# phoreo.net
KiCad netlist of a schematic drawn in EAGLE
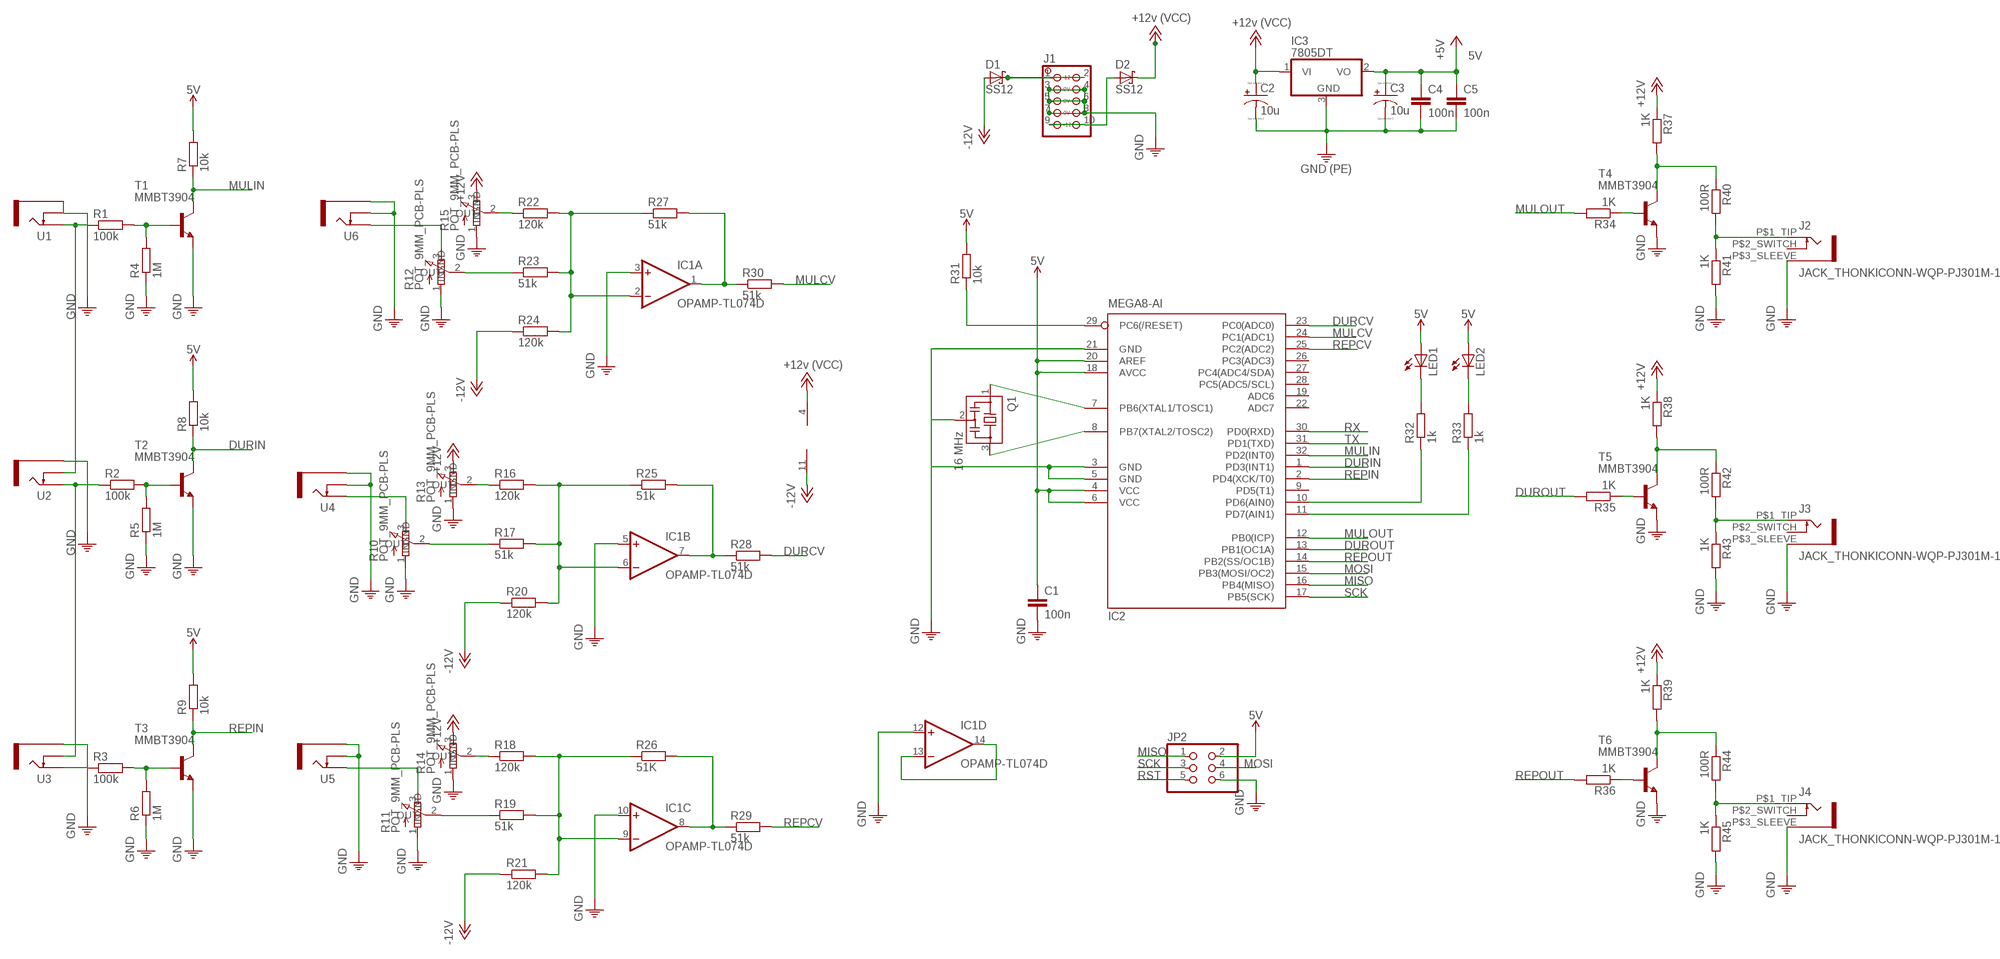
[diagram p0: schematic, sheet 1]

(export (version "E")
  (design (tool "Eeschema 10.0.6"))
  (components
    (comp (ref "C1")
      (value "100n")
      (footprint "eagle-import:C0603K")
      (libsource (lib "eagle-import") (part "CAPACITOR-EUC0603K"))
    )
    (comp (ref "C2")
      (value "10u")
      (footprint "eagle-import:PANASONIC_B")
      (libsource (lib "eagle-import") (part "CAPACITOR_POLARIZED-USB"))
    )
    (comp (ref "C3")
      (value "10u")
      (footprint "eagle-import:PANASONIC_B")
      (libsource (lib "eagle-import") (part "CAPACITOR_POLARIZED-USB"))
    )
    (comp (ref "C4")
      (value "100n")
      (footprint "eagle-import:C0603")
      (libsource (lib "eagle-import") (part "CAPACITOR-EUC0603"))
    )
    (comp (ref "C5")
      (value "100n")
      (footprint "eagle-import:C0603")
      (libsource (lib "eagle-import") (part "CAPACITOR-EUC0603"))
    )
    (comp (ref "D1")
      (value "SS12")
      (footprint "eagle-import:SMA_DO214AC")
      (libsource (lib "eagle-import") (part "D_SCHOTTKY-SMA"))
    )
    (comp (ref "D2")
      (value "SS12")
      (footprint "eagle-import:SMA_DO214AC")
      (libsource (lib "eagle-import") (part "D_SCHOTTKY-SMA"))
    )
    (comp (ref "IC1")
      (value "OPAMP-TL074D")
      (footprint "eagle-import:SO14")
      (libsource (lib "eagle-import") (part "OPAMP-TL074D"))
    )
    (comp (ref "IC2")
      (value "MEGA8-AI")
      (footprint "eagle-import:TQFP32-08")
      (fields (field (name "MPN") "ATMEGA8-16AU"))
      (libsource (lib "eagle-import") (part "MEGA8-AI"))
    )
    (comp (ref "IC3")
      (value "7805DT")
      (footprint "eagle-import:TO252")
      (libsource (lib "eagle-import") (part "78DT05"))
    )
    (comp (ref "J1")
      (value "HEADER-EUROPWR_2X05-OPEN")
      (footprint "eagle-import:2X05_EUROPWR_OPEN")
      (libsource (lib "eagle-import") (part "HEADER-EUROPWR_2X05-OPEN"))
    )
    (comp (ref "J2")
      (value "JACK_THONKICONN-WQP-PJ301M-12")
      (footprint "eagle-import:WQP-PJ301M-12_JACK")
      (libsource (lib "eagle-import") (part "JACK_THONKICONN-WQP-PJ301M-12"))
    )
    (comp (ref "J3")
      (value "JACK_THONKICONN-WQP-PJ301M-12")
      (footprint "eagle-import:WQP-PJ301M-12_JACK")
      (libsource (lib "eagle-import") (part "JACK_THONKICONN-WQP-PJ301M-12"))
    )
    (comp (ref "J4")
      (value "JACK_THONKICONN-WQP-PJ301M-12")
      (footprint "eagle-import:WQP-PJ301M-12_JACK")
      (libsource (lib "eagle-import") (part "JACK_THONKICONN-WQP-PJ301M-12"))
    )
    (comp (ref "JP2")
      (value "PINHD-2X3")
      (footprint "eagle-import:2X03")
      (libsource (lib "eagle-import") (part "PINHD-2X3"))
    )
    (comp (ref "LED1")
      (value "LED3MM")
      (footprint "eagle-import:LED3MM")
      (libsource (lib "eagle-import") (part "LED3MM"))
    )
    (comp (ref "LED2")
      (value "LED3MM")
      (footprint "eagle-import:LED3MM")
      (libsource (lib "eagle-import") (part "LED3MM"))
    )
    (comp (ref "Q1")
      (value "16 MHz")
      (footprint "eagle-import:CSTCR6M")
      (fields (field (name "MPN") "CSTCR6M00G53-R0"))
      (libsource (lib "eagle-import") (part "CSTCR6M00G53Z"))
    )
    (comp (ref "R1")
      (value "100k")
      (footprint "eagle-import:R0603")
      (libsource (lib "eagle-import") (part "RESISTOR-EU_R0603"))
    )
    (comp (ref "R2")
      (value "100k")
      (footprint "eagle-import:R0603")
      (libsource (lib "eagle-import") (part "RESISTOR-EU_R0603"))
    )
    (comp (ref "R3")
      (value "100k")
      (footprint "eagle-import:R0603")
      (libsource (lib "eagle-import") (part "RESISTOR-EU_R0603"))
    )
    (comp (ref "R4")
      (value "1M")
      (footprint "eagle-import:R0603")
      (libsource (lib "eagle-import") (part "RESISTOR-EU_R0603"))
    )
    (comp (ref "R5")
      (value "1M")
      (footprint "eagle-import:R0603")
      (libsource (lib "eagle-import") (part "RESISTOR-EU_R0603"))
    )
    (comp (ref "R6")
      (value "1M")
      (footprint "eagle-import:R0603")
      (libsource (lib "eagle-import") (part "RESISTOR-EU_R0603"))
    )
    (comp (ref "R7")
      (value "10k")
      (footprint "eagle-import:R0603")
      (libsource (lib "eagle-import") (part "RESISTOR-EU_R0603"))
    )
    (comp (ref "R8")
      (value "10k")
      (footprint "eagle-import:R0603")
      (libsource (lib "eagle-import") (part "RESISTOR-EU_R0603"))
    )
    (comp (ref "R9")
      (value "10k")
      (footprint "eagle-import:R0603")
      (libsource (lib "eagle-import") (part "RESISTOR-EU_R0603"))
    )
    (comp (ref "R10")
      (value "POT_9MM_PCB-PLS")
      (footprint "eagle-import:9MM_PLS")
      (libsource (lib "eagle-import") (part "POT_9MM_PCB-PLS"))
    )
    (comp (ref "R11")
      (value "POT_9MM_PCB-PLS")
      (footprint "eagle-import:9MM_PLS")
      (libsource (lib "eagle-import") (part "POT_9MM_PCB-PLS"))
    )
    (comp (ref "R12")
      (value "POT_9MM_PCB-PLS")
      (footprint "eagle-import:9MM_PLS")
      (libsource (lib "eagle-import") (part "POT_9MM_PCB-PLS"))
    )
    (comp (ref "R13")
      (value "POT_9MM_PCB-PLS")
      (footprint "eagle-import:9MM_PLS")
      (libsource (lib "eagle-import") (part "POT_9MM_PCB-PLS"))
    )
    (comp (ref "R14")
      (value "POT_9MM_PCB-PLS")
      (footprint "eagle-import:9MM_PLS")
      (libsource (lib "eagle-import") (part "POT_9MM_PCB-PLS"))
    )
    (comp (ref "R15")
      (value "POT_9MM_PCB-PLS")
      (footprint "eagle-import:9MM_PLS")
      (libsource (lib "eagle-import") (part "POT_9MM_PCB-PLS"))
    )
    (comp (ref "R16")
      (value "120k")
      (footprint "eagle-import:R0603")
      (libsource (lib "eagle-import") (part "RESISTOR-EU_R0603"))
    )
    (comp (ref "R17")
      (value "51k")
      (footprint "eagle-import:R0603")
      (libsource (lib "eagle-import") (part "RESISTOR-EU_R0603"))
    )
    (comp (ref "R18")
      (value "120k")
      (footprint "eagle-import:R0603")
      (libsource (lib "eagle-import") (part "RESISTOR-EU_R0603"))
    )
    (comp (ref "R19")
      (value "51k")
      (footprint "eagle-import:R0603")
      (libsource (lib "eagle-import") (part "RESISTOR-EU_R0603"))
    )
    (comp (ref "R20")
      (value "120k")
      (footprint "eagle-import:R0603")
      (libsource (lib "eagle-import") (part "RESISTOR-EU_R0603"))
    )
    (comp (ref "R21")
      (value "120k")
      (footprint "eagle-import:R0603")
      (libsource (lib "eagle-import") (part "RESISTOR-EU_R0603"))
    )
    (comp (ref "R22")
      (value "120k")
      (footprint "eagle-import:R0603")
      (libsource (lib "eagle-import") (part "RESISTOR-EU_R0603"))
    )
    (comp (ref "R23")
      (value "51k")
      (footprint "eagle-import:R0603")
      (libsource (lib "eagle-import") (part "RESISTOR-EU_R0603"))
    )
    (comp (ref "R24")
      (value "120k")
      (footprint "eagle-import:R0603")
      (libsource (lib "eagle-import") (part "RESISTOR-EU_R0603"))
    )
    (comp (ref "R25")
      (value "51k")
      (footprint "eagle-import:R0603")
      (libsource (lib "eagle-import") (part "RESISTOR-EU_R0603"))
    )
    (comp (ref "R26")
      (value "51K")
      (footprint "eagle-import:R0603")
      (libsource (lib "eagle-import") (part "RESISTOR-EU_R0603"))
    )
    (comp (ref "R27")
      (value "51k")
      (footprint "eagle-import:R0603")
      (libsource (lib "eagle-import") (part "RESISTOR-EU_R0603"))
    )
    (comp (ref "R28")
      (value "51k")
      (footprint "eagle-import:R0603")
      (libsource (lib "eagle-import") (part "RESISTOR-EU_R0603"))
    )
    (comp (ref "R29")
      (value "51k")
      (footprint "eagle-import:R0603")
      (libsource (lib "eagle-import") (part "RESISTOR-EU_R0603"))
    )
    (comp (ref "R30")
      (value "51k")
      (footprint "eagle-import:R0603")
      (libsource (lib "eagle-import") (part "RESISTOR-EU_R0603"))
    )
    (comp (ref "R31")
      (value "10k")
      (footprint "eagle-import:R0603")
      (libsource (lib "eagle-import") (part "RESISTOR-EU_R0603"))
    )
    (comp (ref "R32")
      (value "1k")
      (footprint "eagle-import:R0603")
      (libsource (lib "eagle-import") (part "RESISTOR-EU_R0603"))
    )
    (comp (ref "R33")
      (value "1k")
      (footprint "eagle-import:R0603")
      (libsource (lib "eagle-import") (part "RESISTOR-EU_R0603"))
    )
    (comp (ref "R34")
      (value "1K")
      (footprint "eagle-import:R0603")
      (libsource (lib "eagle-import") (part "RESISTOR-EU_R0603"))
    )
    (comp (ref "R35")
      (value "1K")
      (footprint "eagle-import:R0603")
      (libsource (lib "eagle-import") (part "RESISTOR-EU_R0603"))
    )
    (comp (ref "R36")
      (value "1K")
      (footprint "eagle-import:R0603")
      (libsource (lib "eagle-import") (part "RESISTOR-EU_R0603"))
    )
    (comp (ref "R37")
      (value "1K")
      (footprint "eagle-import:R0603")
      (libsource (lib "eagle-import") (part "RESISTOR-EU_R0603"))
    )
    (comp (ref "R38")
      (value "1K")
      (footprint "eagle-import:R0603")
      (libsource (lib "eagle-import") (part "RESISTOR-EU_R0603"))
    )
    (comp (ref "R39")
      (value "1K")
      (footprint "eagle-import:R0603")
      (libsource (lib "eagle-import") (part "RESISTOR-EU_R0603"))
    )
    (comp (ref "R40")
      (value "100R")
      (footprint "eagle-import:R0603")
      (libsource (lib "eagle-import") (part "RESISTOR-EU_R0603"))
    )
    (comp (ref "R41")
      (value "1K")
      (footprint "eagle-import:R0603")
      (libsource (lib "eagle-import") (part "RESISTOR-EU_R0603"))
    )
    (comp (ref "R42")
      (value "100R")
      (footprint "eagle-import:R0603")
      (libsource (lib "eagle-import") (part "RESISTOR-EU_R0603"))
    )
    (comp (ref "R43")
      (value "1K")
      (footprint "eagle-import:R0603")
      (libsource (lib "eagle-import") (part "RESISTOR-EU_R0603"))
    )
    (comp (ref "R44")
      (value "100R")
      (footprint "eagle-import:R0603")
      (libsource (lib "eagle-import") (part "RESISTOR-EU_R0603"))
    )
    (comp (ref "R45")
      (value "1K")
      (footprint "eagle-import:R0603")
      (libsource (lib "eagle-import") (part "RESISTOR-EU_R0603"))
    )
    (comp (ref "T1")
      (value "MMBT3904")
      (footprint "eagle-import:SOT23-BEC")
      (libsource (lib "eagle-import") (part "TRANSISTOR-NPN-SOT23-BECMMBT3904LT1"))
    )
    (comp (ref "T2")
      (value "MMBT3904")
      (footprint "eagle-import:SOT23-BEC")
      (libsource (lib "eagle-import") (part "TRANSISTOR-NPN-SOT23-BECMMBT3904LT1"))
    )
    (comp (ref "T3")
      (value "MMBT3904")
      (footprint "eagle-import:SOT23-BEC")
      (libsource (lib "eagle-import") (part "TRANSISTOR-NPN-SOT23-BECMMBT3904LT1"))
    )
    (comp (ref "T4")
      (value "MMBT3904")
      (footprint "eagle-import:SOT23-BEC")
      (libsource (lib "eagle-import") (part "TRANSISTOR-NPN-SOT23-BECMMBT3904LT1"))
    )
    (comp (ref "T5")
      (value "MMBT3904")
      (footprint "eagle-import:SOT23-BEC")
      (libsource (lib "eagle-import") (part "TRANSISTOR-NPN-SOT23-BECMMBT3904LT1"))
    )
    (comp (ref "T6")
      (value "MMBT3904")
      (footprint "eagle-import:SOT23-BEC")
      (libsource (lib "eagle-import") (part "TRANSISTOR-NPN-SOT23-BECMMBT3904LT1"))
    )
    (comp (ref "U1")
      (value "mulcv")
      (footprint "eagle-import:WQP-PJ301M-12_JACK")
      (libsource (lib "eagle-import") (part "JACK_THONKICONNNEW"))
    )
    (comp (ref "U2")
      (value "mulcv")
      (footprint "eagle-import:WQP-PJ301M-12_JACK")
      (libsource (lib "eagle-import") (part "JACK_THONKICONNNEW"))
    )
    (comp (ref "U3")
      (value "mulcv")
      (footprint "eagle-import:WQP-PJ301M-12_JACK")
      (libsource (lib "eagle-import") (part "JACK_THONKICONNNEW"))
    )
    (comp (ref "U4")
      (value "mulcv")
      (footprint "eagle-import:WQP-PJ301M-12_JACK")
      (libsource (lib "eagle-import") (part "JACK_THONKICONNNEW"))
    )
    (comp (ref "U5")
      (value "mulcv")
      (footprint "eagle-import:WQP-PJ301M-12_JACK")
      (libsource (lib "eagle-import") (part "JACK_THONKICONNNEW"))
    )
    (comp (ref "U6")
      (value "mulcv")
      (footprint "eagle-import:WQP-PJ301M-12_JACK")
      (libsource (lib "eagle-import") (part "JACK_THONKICONNNEW"))
    )
  )
  (nets
    (net (code "1") (name "+5V") (class "Default")
      (node (ref "C1") (pin "1") (pinfunction "1_1") (pintype "passive"))
      (node (ref "C3") (pin "+") (pinfunction "+_+") (pintype "passive"))
      (node (ref "C4") (pin "1") (pinfunction "1_1") (pintype "passive"))
      (node (ref "C5") (pin "1") (pinfunction "1_1") (pintype "passive"))
      (node (ref "IC2") (pin "18") (pinfunction "AVCC_18") (pintype "power_in"))
      (node (ref "IC2") (pin "20") (pinfunction "AREF_20") (pintype "passive"))
      (node (ref "IC2") (pin "4") (pinfunction "VCC_4") (pintype "power_in"))
      (node (ref "IC2") (pin "6") (pinfunction "VCC_6") (pintype "power_in"))
      (node (ref "IC3") (pin "2") (pinfunction "VO_2") (pintype "passive"))
      (node (ref "JP2") (pin "2") (pinfunction "2_2") (pintype "passive"))
      (node (ref "LED1") (pin "A") (pinfunction "A_A") (pintype "passive"))
      (node (ref "LED2") (pin "A") (pinfunction "A_A") (pintype "passive"))
      (node (ref "R31") (pin "2") (pinfunction "2_2") (pintype "passive"))
      (node (ref "R7") (pin "2") (pinfunction "2_2") (pintype "passive"))
      (node (ref "R8") (pin "2") (pinfunction "2_2") (pintype "passive"))
      (node (ref "R9") (pin "2") (pinfunction "2_2") (pintype "passive"))
    )
    (net (code "2") (name "+12V") (class "Default")
      (node (ref "C2") (pin "+") (pinfunction "+_+") (pintype "passive"))
      (node (ref "D2") (pin "C") (pinfunction "C_C") (pintype "passive"))
      (node (ref "IC1") (pin "4") (pinfunction "V+_4") (pintype "power_in"))
      (node (ref "IC3") (pin "1") (pinfunction "VI_1") (pintype "input"))
      (node (ref "R13") (pin "3") (pinfunction "IN_3") (pintype "passive"))
      (node (ref "R14") (pin "3") (pinfunction "IN_3") (pintype "passive"))
      (node (ref "R15") (pin "3") (pinfunction "IN_3") (pintype "passive"))
      (node (ref "R37") (pin "1") (pinfunction "1_1") (pintype "passive"))
      (node (ref "R38") (pin "1") (pinfunction "1_1") (pintype "passive"))
      (node (ref "R39") (pin "1") (pinfunction "1_1") (pintype "passive"))
    )
    (net (code "3") (name "-12V") (class "Default")
      (node (ref "D1") (pin "A") (pinfunction "A_A") (pintype "passive"))
      (node (ref "IC1") (pin "11") (pinfunction "V-_11") (pintype "power_in"))
      (node (ref "R20") (pin "1") (pinfunction "1_1") (pintype "passive"))
      (node (ref "R21") (pin "1") (pinfunction "1_1") (pintype "passive"))
      (node (ref "R24") (pin "1") (pinfunction "1_1") (pintype "passive"))
    )
    (net (code "4") (name "/DURCV") (class "Default")
      (node (ref "IC2") (pin "23") (pinfunction "PC0(ADC0)_23") (pintype "bidirectional"))
      (node (ref "R28") (pin "2") (pinfunction "2_2") (pintype "passive"))
    )
    (net (code "5") (name "/DURIN") (class "Default")
      (node (ref "IC2") (pin "1") (pinfunction "PD3(INT1)_1") (pintype "bidirectional"))
      (node (ref "R8") (pin "1") (pinfunction "1_1") (pintype "passive"))
      (node (ref "T2") (pin "C") (pinfunction "C_C") (pintype "passive"))
    )
    (net (code "6") (name "/DUROUT") (class "Default")
      (node (ref "IC2") (pin "13") (pinfunction "PB1(OC1A)_13") (pintype "bidirectional"))
      (node (ref "R35") (pin "2") (pinfunction "2_2") (pintype "passive"))
    )
    (net (code "7") (name "/MISO") (class "Default")
      (node (ref "IC2") (pin "16") (pinfunction "PB4(MISO)_16") (pintype "bidirectional"))
      (node (ref "JP2") (pin "1") (pinfunction "1_1") (pintype "passive"))
    )
    (net (code "8") (name "/MOSI") (class "Default")
      (node (ref "IC2") (pin "15") (pinfunction "PB3(MOSI/OC2)_15") (pintype "bidirectional"))
      (node (ref "JP2") (pin "4") (pinfunction "4_4") (pintype "passive"))
    )
    (net (code "9") (name "/MULCV") (class "Default")
      (node (ref "IC2") (pin "24") (pinfunction "PC1(ADC1)_24") (pintype "bidirectional"))
      (node (ref "R30") (pin "2") (pinfunction "2_2") (pintype "passive"))
    )
    (net (code "10") (name "/MULIN") (class "Default")
      (node (ref "IC2") (pin "32") (pinfunction "PD2(INT0)_32") (pintype "bidirectional"))
      (node (ref "R7") (pin "1") (pinfunction "1_1") (pintype "passive"))
      (node (ref "T1") (pin "C") (pinfunction "C_C") (pintype "passive"))
    )
    (net (code "11") (name "/MULOUT") (class "Default")
      (node (ref "IC2") (pin "12") (pinfunction "PB0(ICP)_12") (pintype "bidirectional"))
      (node (ref "R34") (pin "2") (pinfunction "2_2") (pintype "passive"))
    )
    (net (code "12") (name "/REPCV") (class "Default")
      (node (ref "IC2") (pin "25") (pinfunction "PC2(ADC2)_25") (pintype "bidirectional"))
      (node (ref "R29") (pin "2") (pinfunction "2_2") (pintype "passive"))
    )
    (net (code "13") (name "/REPIN") (class "Default")
      (node (ref "IC2") (pin "2") (pinfunction "PD4(XCK/T0)_2") (pintype "bidirectional"))
      (node (ref "R9") (pin "1") (pinfunction "1_1") (pintype "passive"))
      (node (ref "T3") (pin "C") (pinfunction "C_C") (pintype "passive"))
    )
    (net (code "14") (name "/REPOUT") (class "Default")
      (node (ref "IC2") (pin "14") (pinfunction "PB2(SS/OC1B)_14") (pintype "bidirectional"))
      (node (ref "R36") (pin "2") (pinfunction "2_2") (pintype "passive"))
    )
    (net (code "15") (name "/RST") (class "Default")
      (node (ref "JP2") (pin "5") (pinfunction "5_5") (pintype "passive"))
    )
    (net (code "16") (name "/RX") (class "Default")
      (node (ref "IC2") (pin "30") (pinfunction "PD0(RXD)_30") (pintype "bidirectional"))
    )
    (net (code "17") (name "/SCK") (class "Default")
      (node (ref "IC2") (pin "17") (pinfunction "PB5(SCK)_17") (pintype "bidirectional"))
      (node (ref "JP2") (pin "3") (pinfunction "3_3") (pintype "passive"))
    )
    (net (code "18") (name "/TX") (class "Default")
      (node (ref "IC2") (pin "31") (pinfunction "PD1(TXD)_31") (pintype "bidirectional"))
    )
    (net (code "19") (name "GND") (class "Default")
      (node (ref "C1") (pin "2") (pinfunction "2_2") (pintype "passive"))
      (node (ref "C2") (pin "-") (pinfunction "-_-") (pintype "passive"))
      (node (ref "C3") (pin "-") (pinfunction "-_-") (pintype "passive"))
      (node (ref "C4") (pin "2") (pinfunction "2_2") (pintype "passive"))
      (node (ref "C5") (pin "2") (pinfunction "2_2") (pintype "passive"))
      (node (ref "IC1") (pin "10") (pinfunction "+IN_10") (pintype "input"))
      (node (ref "IC1") (pin "12") (pinfunction "+IN_12") (pintype "input"))
      (node (ref "IC1") (pin "3") (pinfunction "+IN_3") (pintype "input"))
      (node (ref "IC1") (pin "5") (pinfunction "+IN_5") (pintype "input"))
      (node (ref "IC2") (pin "21") (pinfunction "GND_21") (pintype "power_in"))
      (node (ref "IC2") (pin "3") (pinfunction "GND_3") (pintype "power_in"))
      (node (ref "IC2") (pin "5") (pinfunction "GND_5") (pintype "power_in"))
      (node (ref "IC3") (pin "3") (pinfunction "GND_3") (pintype "passive"))
      (node (ref "J1") (pin "3") (pinfunction "3_3") (pintype "passive"))
      (node (ref "J1") (pin "4") (pinfunction "4_4") (pintype "passive"))
      (node (ref "J1") (pin "5") (pinfunction "5_5") (pintype "passive"))
      (node (ref "J1") (pin "6") (pinfunction "6_6") (pintype "passive"))
      (node (ref "J1") (pin "7") (pinfunction "7_7") (pintype "passive"))
      (node (ref "J1") (pin "8") (pinfunction "8_8") (pintype "passive"))
      (node (ref "J2") (pin "P$3_SLEEVE") (pinfunction "1_P$3_SLEEVE") (pintype "passive"))
      (node (ref "J3") (pin "P$3_SLEEVE") (pinfunction "1_P$3_SLEEVE") (pintype "passive"))
      (node (ref "J4") (pin "P$3_SLEEVE") (pinfunction "1_P$3_SLEEVE") (pintype "passive"))
      (node (ref "JP2") (pin "6") (pinfunction "6_6") (pintype "passive"))
      (node (ref "Q1") (pin "2") (pinfunction "2_2") (pintype "passive"))
      (node (ref "R10") (pin "1") (pinfunction "GND_1") (pintype "passive"))
      (node (ref "R11") (pin "1") (pinfunction "GND_1") (pintype "passive"))
      (node (ref "R12") (pin "1") (pinfunction "GND_1") (pintype "passive"))
      (node (ref "R13") (pin "1") (pinfunction "GND_1") (pintype "passive"))
      (node (ref "R14") (pin "1") (pinfunction "GND_1") (pintype "passive"))
      (node (ref "R15") (pin "1") (pinfunction "GND_1") (pintype "passive"))
      (node (ref "R4") (pin "1") (pinfunction "1_1") (pintype "passive"))
      (node (ref "R41") (pin "2") (pinfunction "2_2") (pintype "passive"))
      (node (ref "R43") (pin "2") (pinfunction "2_2") (pintype "passive"))
      (node (ref "R45") (pin "2") (pinfunction "2_2") (pintype "passive"))
      (node (ref "R5") (pin "1") (pinfunction "1_1") (pintype "passive"))
      (node (ref "R6") (pin "1") (pinfunction "1_1") (pintype "passive"))
      (node (ref "T1") (pin "E") (pinfunction "E_E") (pintype "passive"))
      (node (ref "T2") (pin "E") (pinfunction "E_E") (pintype "passive"))
      (node (ref "T3") (pin "E") (pinfunction "E_E") (pintype "passive"))
      (node (ref "T4") (pin "E") (pinfunction "E_E") (pintype "passive"))
      (node (ref "T5") (pin "E") (pinfunction "E_E") (pintype "passive"))
      (node (ref "T6") (pin "E") (pinfunction "E_E") (pintype "passive"))
      (node (ref "U1") (pin "P$2_SWITCH") (pinfunction "SWITCH_P$2_SWITCH") (pintype "passive"))
      (node (ref "U1") (pin "P$3_SLEEVE") (pinfunction "SLEEVE_P$3_SLEEVE") (pintype "passive"))
      (node (ref "U2") (pin "P$3_SLEEVE") (pinfunction "SLEEVE_P$3_SLEEVE") (pintype "passive"))
      (node (ref "U3") (pin "P$3_SLEEVE") (pinfunction "SLEEVE_P$3_SLEEVE") (pintype "passive"))
      (node (ref "U4") (pin "P$2_SWITCH") (pinfunction "SWITCH_P$2_SWITCH") (pintype "passive"))
      (node (ref "U4") (pin "P$3_SLEEVE") (pinfunction "SLEEVE_P$3_SLEEVE") (pintype "passive"))
      (node (ref "U5") (pin "P$2_SWITCH") (pinfunction "SWITCH_P$2_SWITCH") (pintype "passive"))
      (node (ref "U5") (pin "P$3_SLEEVE") (pinfunction "SLEEVE_P$3_SLEEVE") (pintype "passive"))
      (node (ref "U6") (pin "P$2_SWITCH") (pinfunction "SWITCH_P$2_SWITCH") (pintype "passive"))
      (node (ref "U6") (pin "P$3_SLEEVE") (pinfunction "SLEEVE_P$3_SLEEVE") (pintype "passive"))
    )
    (net (code "20") (name "Net-(D1-PadC)") (class "Default")
      (node (ref "D1") (pin "C") (pinfunction "C_C") (pintype "passive"))
      (node (ref "J1") (pin "1") (pinfunction "1_1") (pintype "passive"))
      (node (ref "J1") (pin "2") (pinfunction "2_2") (pintype "passive"))
    )
    (net (code "21") (name "Net-(D2-PadA)") (class "Default")
      (node (ref "D2") (pin "A") (pinfunction "A_A") (pintype "passive"))
      (node (ref "J1") (pin "10") (pinfunction "10_10") (pintype "passive"))
      (node (ref "J1") (pin "9") (pinfunction "9_9") (pintype "passive"))
    )
    (net (code "22") (name "Net-(IC1A--IN)") (class "Default")
      (node (ref "IC1") (pin "2") (pinfunction "-IN_2") (pintype "input"))
      (node (ref "R22") (pin "2") (pinfunction "2_2") (pintype "passive"))
      (node (ref "R23") (pin "2") (pinfunction "2_2") (pintype "passive"))
      (node (ref "R24") (pin "2") (pinfunction "2_2") (pintype "passive"))
      (node (ref "R27") (pin "1") (pinfunction "1_1") (pintype "passive"))
    )
    (net (code "23") (name "Net-(IC1A-OUT)") (class "Default")
      (node (ref "IC1") (pin "1") (pinfunction "OUT_1") (pintype "output"))
      (node (ref "R27") (pin "2") (pinfunction "2_2") (pintype "passive"))
      (node (ref "R30") (pin "1") (pinfunction "1_1") (pintype "passive"))
    )
    (net (code "24") (name "Net-(IC1B--IN)") (class "Default")
      (node (ref "IC1") (pin "6") (pinfunction "-IN_6") (pintype "input"))
      (node (ref "R16") (pin "2") (pinfunction "2_2") (pintype "passive"))
      (node (ref "R17") (pin "2") (pinfunction "2_2") (pintype "passive"))
      (node (ref "R20") (pin "2") (pinfunction "2_2") (pintype "passive"))
      (node (ref "R25") (pin "1") (pinfunction "1_1") (pintype "passive"))
    )
    (net (code "25") (name "Net-(IC1B-OUT)") (class "Default")
      (node (ref "IC1") (pin "7") (pinfunction "OUT_7") (pintype "output"))
      (node (ref "R25") (pin "2") (pinfunction "2_2") (pintype "passive"))
      (node (ref "R28") (pin "1") (pinfunction "1_1") (pintype "passive"))
    )
    (net (code "26") (name "Net-(IC1C--IN)") (class "Default")
      (node (ref "IC1") (pin "9") (pinfunction "-IN_9") (pintype "input"))
      (node (ref "R18") (pin "2") (pinfunction "2_2") (pintype "passive"))
      (node (ref "R19") (pin "2") (pinfunction "2_2") (pintype "passive"))
      (node (ref "R21") (pin "2") (pinfunction "2_2") (pintype "passive"))
      (node (ref "R26") (pin "1") (pinfunction "1_1") (pintype "passive"))
    )
    (net (code "27") (name "Net-(IC1C-OUT)") (class "Default")
      (node (ref "IC1") (pin "8") (pinfunction "OUT_8") (pintype "output"))
      (node (ref "R26") (pin "2") (pinfunction "2_2") (pintype "passive"))
      (node (ref "R29") (pin "1") (pinfunction "1_1") (pintype "passive"))
    )
    (net (code "28") (name "Net-(IC1D--IN)") (class "Default")
      (node (ref "IC1") (pin "13") (pinfunction "-IN_13") (pintype "input"))
      (node (ref "IC1") (pin "14") (pinfunction "OUT_14") (pintype "output"))
    )
    (net (code "29") (name "Net-(IC2-PB6(XTAL1{slash}TOSC1))") (class "Default")
      (node (ref "IC2") (pin "7") (pinfunction "PB6(XTAL1/TOSC1)_7") (pintype "bidirectional"))
      (node (ref "Q1") (pin "1") (pinfunction "1_1") (pintype "passive"))
    )
    (net (code "30") (name "Net-(IC2-PB7(XTAL2{slash}TOSC2))") (class "Default")
      (node (ref "IC2") (pin "8") (pinfunction "PB7(XTAL2/TOSC2)_8") (pintype "bidirectional"))
      (node (ref "Q1") (pin "3") (pinfunction "3_3") (pintype "passive"))
    )
    (net (code "31") (name "Net-(IC2-PC6({slash}RESET))") (class "Default")
      (node (ref "IC2") (pin "29") (pinfunction "PC6(/RESET)_29") (pintype "bidirectional"))
      (node (ref "R31") (pin "1") (pinfunction "1_1") (pintype "passive"))
    )
    (net (code "32") (name "Net-(IC2-PD6(AIN0))") (class "Default")
      (node (ref "IC2") (pin "10") (pinfunction "PD6(AIN0)_10") (pintype "bidirectional"))
      (node (ref "R32") (pin "1") (pinfunction "1_1") (pintype "passive"))
    )
    (net (code "33") (name "Net-(IC2-PD7(AIN1))") (class "Default")
      (node (ref "IC2") (pin "11") (pinfunction "PD7(AIN1)_11") (pintype "bidirectional"))
      (node (ref "R33") (pin "1") (pinfunction "1_1") (pintype "passive"))
    )
    (net (code "34") (name "Net-(J2-2)") (class "Default")
      (node (ref "J2") (pin "P$1_TIP") (pinfunction "2_P$1_TIP") (pintype "passive"))
      (node (ref "R40") (pin "2") (pinfunction "2_2") (pintype "passive"))
      (node (ref "R41") (pin "1") (pinfunction "1_1") (pintype "passive"))
    )
    (net (code "35") (name "Net-(J3-2)") (class "Default")
      (node (ref "J3") (pin "P$1_TIP") (pinfunction "2_P$1_TIP") (pintype "passive"))
      (node (ref "R42") (pin "2") (pinfunction "2_2") (pintype "passive"))
      (node (ref "R43") (pin "1") (pinfunction "1_1") (pintype "passive"))
    )
    (net (code "36") (name "Net-(J4-2)") (class "Default")
      (node (ref "J4") (pin "P$1_TIP") (pinfunction "2_P$1_TIP") (pintype "passive"))
      (node (ref "R44") (pin "2") (pinfunction "2_2") (pintype "passive"))
      (node (ref "R45") (pin "1") (pinfunction "1_1") (pintype "passive"))
    )
    (net (code "37") (name "Net-(LED1-C)") (class "Default")
      (node (ref "LED1") (pin "K") (pinfunction "C_K") (pintype "passive"))
      (node (ref "R32") (pin "2") (pinfunction "2_2") (pintype "passive"))
    )
    (net (code "38") (name "Net-(LED2-C)") (class "Default")
      (node (ref "LED2") (pin "K") (pinfunction "C_K") (pintype "passive"))
      (node (ref "R33") (pin "2") (pinfunction "2_2") (pintype "passive"))
    )
    (net (code "39") (name "Net-(R1-Pad2)") (class "Default")
      (node (ref "R1") (pin "2") (pinfunction "2_2") (pintype "passive"))
      (node (ref "R4") (pin "2") (pinfunction "2_2") (pintype "passive"))
      (node (ref "T1") (pin "B") (pinfunction "B_B") (pintype "passive"))
    )
    (net (code "40") (name "Net-(R2-Pad2)") (class "Default")
      (node (ref "R2") (pin "2") (pinfunction "2_2") (pintype "passive"))
      (node (ref "R5") (pin "2") (pinfunction "2_2") (pintype "passive"))
      (node (ref "T2") (pin "B") (pinfunction "B_B") (pintype "passive"))
    )
    (net (code "41") (name "Net-(R3-Pad2)") (class "Default")
      (node (ref "R3") (pin "2") (pinfunction "2_2") (pintype "passive"))
      (node (ref "R6") (pin "2") (pinfunction "2_2") (pintype "passive"))
      (node (ref "T3") (pin "B") (pinfunction "B_B") (pintype "passive"))
    )
    (net (code "42") (name "Net-(R10-IN)") (class "Default")
      (node (ref "R10") (pin "3") (pinfunction "IN_3") (pintype "passive"))
      (node (ref "U4") (pin "P$1_TIP") (pinfunction "TIP_P$1_TIP") (pintype "passive"))
    )
    (net (code "43") (name "Net-(R10-OUT)") (class "Default")
      (node (ref "R10") (pin "2") (pinfunction "OUT_2") (pintype "passive"))
      (node (ref "R17") (pin "1") (pinfunction "1_1") (pintype "passive"))
    )
    (net (code "44") (name "Net-(R11-IN)") (class "Default")
      (node (ref "R11") (pin "3") (pinfunction "IN_3") (pintype "passive"))
      (node (ref "U5") (pin "P$1_TIP") (pinfunction "TIP_P$1_TIP") (pintype "passive"))
    )
    (net (code "45") (name "Net-(R11-OUT)") (class "Default")
      (node (ref "R11") (pin "2") (pinfunction "OUT_2") (pintype "passive"))
      (node (ref "R19") (pin "1") (pinfunction "1_1") (pintype "passive"))
    )
    (net (code "46") (name "Net-(R12-IN)") (class "Default")
      (node (ref "R12") (pin "3") (pinfunction "IN_3") (pintype "passive"))
      (node (ref "U6") (pin "P$1_TIP") (pinfunction "TIP_P$1_TIP") (pintype "passive"))
    )
    (net (code "47") (name "Net-(R12-OUT)") (class "Default")
      (node (ref "R12") (pin "2") (pinfunction "OUT_2") (pintype "passive"))
      (node (ref "R23") (pin "1") (pinfunction "1_1") (pintype "passive"))
    )
    (net (code "48") (name "Net-(R13-OUT)") (class "Default")
      (node (ref "R13") (pin "2") (pinfunction "OUT_2") (pintype "passive"))
      (node (ref "R16") (pin "1") (pinfunction "1_1") (pintype "passive"))
    )
    (net (code "49") (name "Net-(R14-OUT)") (class "Default")
      (node (ref "R14") (pin "2") (pinfunction "OUT_2") (pintype "passive"))
      (node (ref "R18") (pin "1") (pinfunction "1_1") (pintype "passive"))
    )
    (net (code "50") (name "Net-(R15-OUT)") (class "Default")
      (node (ref "R15") (pin "2") (pinfunction "OUT_2") (pintype "passive"))
      (node (ref "R22") (pin "1") (pinfunction "1_1") (pintype "passive"))
    )
    (net (code "51") (name "Net-(R34-Pad1)") (class "Default")
      (node (ref "R34") (pin "1") (pinfunction "1_1") (pintype "passive"))
      (node (ref "T4") (pin "B") (pinfunction "B_B") (pintype "passive"))
    )
    (net (code "52") (name "Net-(R35-Pad1)") (class "Default")
      (node (ref "R35") (pin "1") (pinfunction "1_1") (pintype "passive"))
      (node (ref "T5") (pin "B") (pinfunction "B_B") (pintype "passive"))
    )
    (net (code "53") (name "Net-(R36-Pad1)") (class "Default")
      (node (ref "R36") (pin "1") (pinfunction "1_1") (pintype "passive"))
      (node (ref "T6") (pin "B") (pinfunction "B_B") (pintype "passive"))
    )
    (net (code "54") (name "Net-(R37-Pad2)") (class "Default")
      (node (ref "R37") (pin "2") (pinfunction "2_2") (pintype "passive"))
      (node (ref "R40") (pin "1") (pinfunction "1_1") (pintype "passive"))
      (node (ref "T4") (pin "C") (pinfunction "C_C") (pintype "passive"))
    )
    (net (code "55") (name "Net-(R38-Pad2)") (class "Default")
      (node (ref "R38") (pin "2") (pinfunction "2_2") (pintype "passive"))
      (node (ref "R42") (pin "1") (pinfunction "1_1") (pintype "passive"))
      (node (ref "T5") (pin "C") (pinfunction "C_C") (pintype "passive"))
    )
    (net (code "56") (name "Net-(R39-Pad2)") (class "Default")
      (node (ref "R39") (pin "2") (pinfunction "2_2") (pintype "passive"))
      (node (ref "R44") (pin "1") (pinfunction "1_1") (pintype "passive"))
      (node (ref "T6") (pin "C") (pinfunction "C_C") (pintype "passive"))
    )
    (net (code "57") (name "Net-(U1-TIP)") (class "Default")
      (node (ref "R1") (pin "1") (pinfunction "1_1") (pintype "passive"))
      (node (ref "U1") (pin "P$1_TIP") (pinfunction "TIP_P$1_TIP") (pintype "passive"))
      (node (ref "U2") (pin "P$2_SWITCH") (pinfunction "SWITCH_P$2_SWITCH") (pintype "passive"))
    )
    (net (code "58") (name "Net-(U2-TIP)") (class "Default")
      (node (ref "R2") (pin "1") (pinfunction "1_1") (pintype "passive"))
      (node (ref "U2") (pin "P$1_TIP") (pinfunction "TIP_P$1_TIP") (pintype "passive"))
      (node (ref "U3") (pin "P$2_SWITCH") (pinfunction "SWITCH_P$2_SWITCH") (pintype "passive"))
    )
    (net (code "59") (name "Net-(U3-TIP)") (class "Default")
      (node (ref "R3") (pin "1") (pinfunction "1_1") (pintype "passive"))
      (node (ref "U3") (pin "P$1_TIP") (pinfunction "TIP_P$1_TIP") (pintype "passive"))
    )
    (net (code "60") (name "unconnected-(IC2-ADC6-Pad19)") (class "Default")
      (node (ref "IC2") (pin "19") (pinfunction "ADC6_19") (pintype "bidirectional"))
    )
    (net (code "61") (name "unconnected-(IC2-ADC7-Pad22)") (class "Default")
      (node (ref "IC2") (pin "22") (pinfunction "ADC7_22") (pintype "bidirectional"))
    )
    (net (code "62") (name "unconnected-(IC2-PC3(ADC3)-Pad26)") (class "Default")
      (node (ref "IC2") (pin "26") (pinfunction "PC3(ADC3)_26") (pintype "bidirectional"))
    )
    (net (code "63") (name "unconnected-(IC2-PC4(ADC4{slash}SDA)-Pad27)") (class "Default")
      (node (ref "IC2") (pin "27") (pinfunction "PC4(ADC4/SDA)_27") (pintype "bidirectional"))
    )
    (net (code "64") (name "unconnected-(IC2-PC5(ADC5{slash}SCL)-Pad28)") (class "Default")
      (node (ref "IC2") (pin "28") (pinfunction "PC5(ADC5/SCL)_28") (pintype "bidirectional"))
    )
    (net (code "65") (name "unconnected-(IC2-PD5(T1)-Pad9)") (class "Default")
      (node (ref "IC2") (pin "9") (pinfunction "PD5(T1)_9") (pintype "bidirectional"))
    )
    (net (code "66") (name "unconnected-(J2-3-PadP$2_SWITCH)") (class "Default")
      (node (ref "J2") (pin "P$2_SWITCH") (pinfunction "3_P$2_SWITCH") (pintype "passive"))
    )
    (net (code "67") (name "unconnected-(J3-3-PadP$2_SWITCH)") (class "Default")
      (node (ref "J3") (pin "P$2_SWITCH") (pinfunction "3_P$2_SWITCH") (pintype "passive"))
    )
    (net (code "68") (name "unconnected-(J4-3-PadP$2_SWITCH)") (class "Default")
      (node (ref "J4") (pin "P$2_SWITCH") (pinfunction "3_P$2_SWITCH") (pintype "passive"))
    )
  )
)
